# I2C-SignalTestJig.net
KiCad netlist of a schematic drawn in EAGLE
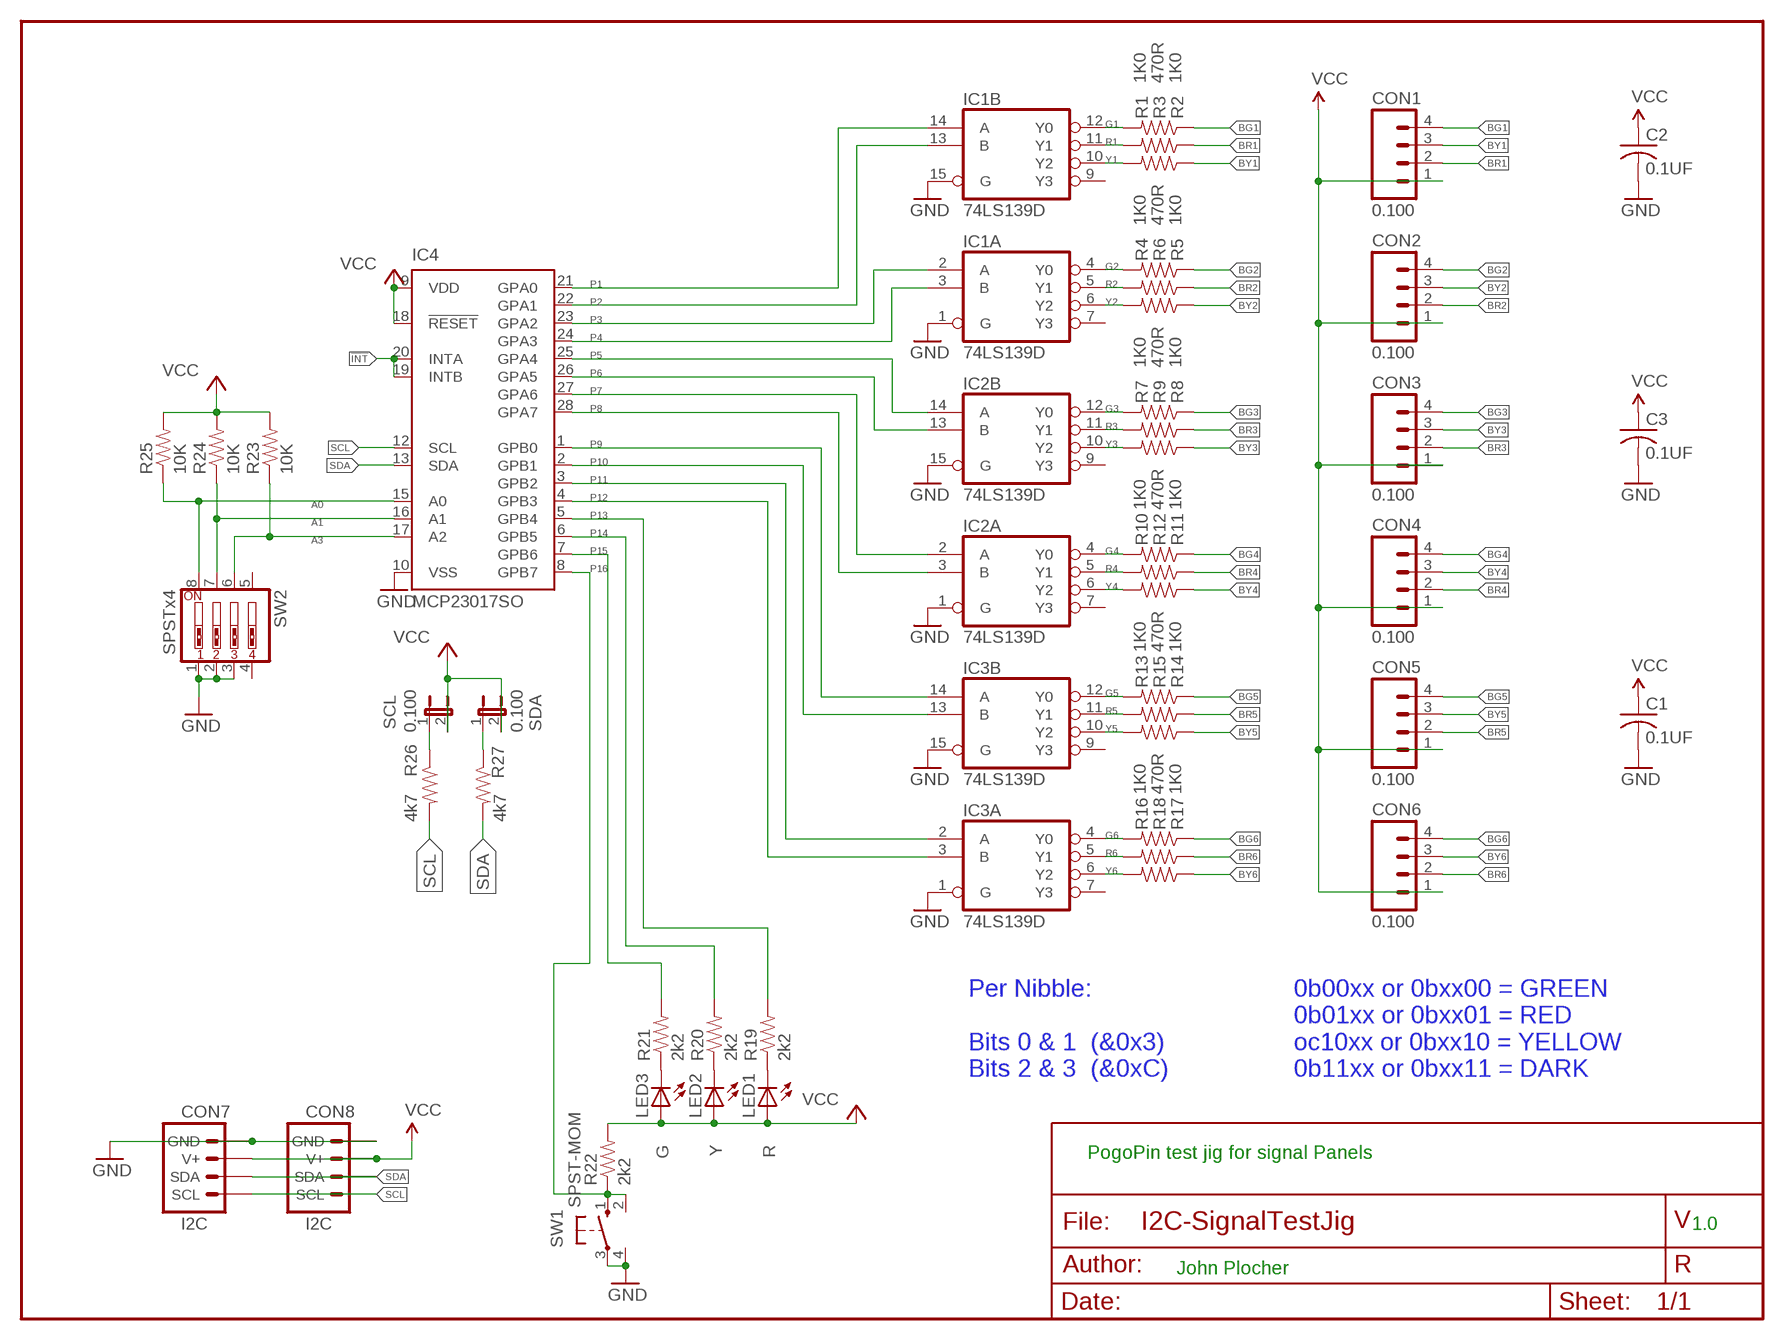
[diagram p0: schematic, sheet 1]

(export (version "E")
  (design (tool "Eeschema 10.0.6"))
  (components
    (comp (ref "C1")
      (value "0.1UF")
      (footprint "eagle-import:0603-CAP")
      (libsource (lib "eagle-import") (part "CAP0603"))
    )
    (comp (ref "C2")
      (value "0.1UF")
      (footprint "eagle-import:0603-CAP")
      (libsource (lib "eagle-import") (part "CAP0603"))
    )
    (comp (ref "C3")
      (value "0.1UF")
      (footprint "eagle-import:0603-CAP")
      (libsource (lib "eagle-import") (part "CAP0603"))
    )
    (comp (ref "CON1")
      (value "0.100")
      (footprint "eagle-import:1X04_LOCK")
      (libsource (lib "eagle-import") (part "CONNECTOR-M04LOCK"))
    )
    (comp (ref "CON2")
      (value "0.100")
      (footprint "eagle-import:1X04_LOCK")
      (libsource (lib "eagle-import") (part "CONNECTOR-M04LOCK"))
    )
    (comp (ref "CON3")
      (value "0.100")
      (footprint "eagle-import:1X04_LOCK")
      (libsource (lib "eagle-import") (part "CONNECTOR-M04LOCK"))
    )
    (comp (ref "CON4")
      (value "0.100")
      (footprint "eagle-import:1X04_LOCK")
      (libsource (lib "eagle-import") (part "CONNECTOR-M04LOCK"))
    )
    (comp (ref "CON5")
      (value "0.100")
      (footprint "eagle-import:1X04_LOCK")
      (libsource (lib "eagle-import") (part "CONNECTOR-M04LOCK"))
    )
    (comp (ref "CON6")
      (value "0.100")
      (footprint "eagle-import:1X04_LOCK")
      (libsource (lib "eagle-import") (part "CONNECTOR-M04LOCK"))
    )
    (comp (ref "CON7")
      (value "I2C")
      (footprint "eagle-import:I2C-L")
      (libsource (lib "eagle-import") (part "CONNECTOR-I2CLEFT"))
    )
    (comp (ref "CON8")
      (value "I2C")
      (footprint "eagle-import:I2C-L")
      (libsource (lib "eagle-import") (part "CONNECTOR-I2CLEFT"))
    )
    (comp (ref "IC1")
      (value "74LS139D")
      (footprint "eagle-import:SO16")
      (libsource (lib "eagle-import") (part "74139DLS"))
    )
    (comp (ref "IC2")
      (value "74LS139D")
      (footprint "eagle-import:SO16")
      (libsource (lib "eagle-import") (part "74139DLS"))
    )
    (comp (ref "IC3")
      (value "74LS139D")
      (footprint "eagle-import:SO16")
      (libsource (lib "eagle-import") (part "74139DLS"))
    )
    (comp (ref "IC4")
      (value "MCP23017SO")
      (footprint "eagle-import:SO28W")
      (fields (field (name "MF") "MICROCHIP") (field (name "MPN") "MCP23017-E/SO"))
      (libsource (lib "eagle-import") (part "MCP23017SO"))
    )
    (comp (ref "LED1")
      (value "R")
      (footprint "eagle-import:0603-LED")
      (libsource (lib "eagle-import") (part "LED0603-LED"))
    )
    (comp (ref "LED2")
      (value "Y")
      (footprint "eagle-import:0603-LED")
      (libsource (lib "eagle-import") (part "LED0603-LED"))
    )
    (comp (ref "LED3")
      (value "G")
      (footprint "eagle-import:0603-LED")
      (libsource (lib "eagle-import") (part "LED0603-LED"))
    )
    (comp (ref "R1")
      (value "1K0")
      (footprint "eagle-import:0805-RES")
      (libsource (lib "eagle-import") (part "R0805-RES"))
    )
    (comp (ref "R2")
      (value "1K0")
      (footprint "eagle-import:0805-RES")
      (libsource (lib "eagle-import") (part "R0805-RES"))
    )
    (comp (ref "R3")
      (value "470R")
      (footprint "eagle-import:0805-RES")
      (libsource (lib "eagle-import") (part "R0805-RES"))
    )
    (comp (ref "R4")
      (value "1K0")
      (footprint "eagle-import:0805-RES")
      (libsource (lib "eagle-import") (part "R0805-RES"))
    )
    (comp (ref "R5")
      (value "1K0")
      (footprint "eagle-import:0805-RES")
      (libsource (lib "eagle-import") (part "R0805-RES"))
    )
    (comp (ref "R6")
      (value "470R")
      (footprint "eagle-import:0805-RES")
      (libsource (lib "eagle-import") (part "R0805-RES"))
    )
    (comp (ref "R7")
      (value "1K0")
      (footprint "eagle-import:0805-RES")
      (libsource (lib "eagle-import") (part "R0805-RES"))
    )
    (comp (ref "R8")
      (value "1K0")
      (footprint "eagle-import:0805-RES")
      (libsource (lib "eagle-import") (part "R0805-RES"))
    )
    (comp (ref "R9")
      (value "470R")
      (footprint "eagle-import:0805-RES")
      (libsource (lib "eagle-import") (part "R0805-RES"))
    )
    (comp (ref "R10")
      (value "1K0")
      (footprint "eagle-import:0805-RES")
      (libsource (lib "eagle-import") (part "R0805-RES"))
    )
    (comp (ref "R11")
      (value "1K0")
      (footprint "eagle-import:0805-RES")
      (libsource (lib "eagle-import") (part "R0805-RES"))
    )
    (comp (ref "R12")
      (value "470R")
      (footprint "eagle-import:0805-RES")
      (libsource (lib "eagle-import") (part "R0805-RES"))
    )
    (comp (ref "R13")
      (value "1K0")
      (footprint "eagle-import:0805-RES")
      (libsource (lib "eagle-import") (part "R0805-RES"))
    )
    (comp (ref "R14")
      (value "1K0")
      (footprint "eagle-import:0805-RES")
      (libsource (lib "eagle-import") (part "R0805-RES"))
    )
    (comp (ref "R15")
      (value "470R")
      (footprint "eagle-import:0805-RES")
      (libsource (lib "eagle-import") (part "R0805-RES"))
    )
    (comp (ref "R16")
      (value "1K0")
      (footprint "eagle-import:0805-RES")
      (libsource (lib "eagle-import") (part "R0805-RES"))
    )
    (comp (ref "R17")
      (value "1K0")
      (footprint "eagle-import:0805-RES")
      (libsource (lib "eagle-import") (part "R0805-RES"))
    )
    (comp (ref "R18")
      (value "470R")
      (footprint "eagle-import:0805-RES")
      (libsource (lib "eagle-import") (part "R0805-RES"))
    )
    (comp (ref "R19")
      (value "2k2")
      (footprint "eagle-import:0603-RES")
      (libsource (lib "eagle-import") (part "R0603-RES"))
    )
    (comp (ref "R20")
      (value "2k2")
      (footprint "eagle-import:0603-RES")
      (libsource (lib "eagle-import") (part "R0603-RES"))
    )
    (comp (ref "R21")
      (value "2k2")
      (footprint "eagle-import:0603-RES")
      (libsource (lib "eagle-import") (part "R0603-RES"))
    )
    (comp (ref "R22")
      (value "2k2")
      (footprint "eagle-import:0603-RES")
      (libsource (lib "eagle-import") (part "R0603-RES"))
    )
    (comp (ref "R23")
      (value "10K")
      (footprint "eagle-import:0603-RES")
      (libsource (lib "eagle-import") (part "R0603-RES"))
    )
    (comp (ref "R24")
      (value "10K")
      (footprint "eagle-import:0603-RES")
      (libsource (lib "eagle-import") (part "R0603-RES"))
    )
    (comp (ref "R25")
      (value "10K")
      (footprint "eagle-import:0603-RES")
      (libsource (lib "eagle-import") (part "R0603-RES"))
    )
    (comp (ref "R26")
      (value "4k7")
      (footprint "eagle-import:0603-RES")
      (libsource (lib "eagle-import") (part "R0603-RES"))
    )
    (comp (ref "R27")
      (value "4k7")
      (footprint "eagle-import:0603-RES")
      (libsource (lib "eagle-import") (part "R0603-RES"))
    )
    (comp (ref "SCL")
      (value "0.100")
      (footprint "eagle-import:1X02_LOCK")
      (libsource (lib "eagle-import") (part "JUMPER-2PTH_LOCK"))
    )
    (comp (ref "SDA")
      (value "0.100")
      (footprint "eagle-import:1X02_LOCK")
      (libsource (lib "eagle-import") (part "JUMPER-2PTH_LOCK"))
    )
    (comp (ref "SW1")
      (value "SPST-MOM")
      (footprint "eagle-import:4P-PTH-6.0X6.0X5.0H")
      (libsource (lib "eagle-import") (part "SWITCH-(ON)SMALLPADS"))
    )
    (comp (ref "SW2")
      (value "SPSTx4")
      (footprint "eagle-import:EDG-04")
      (libsource (lib "eagle-import") (part "SW_DIP-4"))
    )
  )
  (nets
    (net (code "1") (name "/A0") (class "Default")
      (node (ref "IC4") (pin "15") (pinfunction "A0_15") (pintype "input"))
      (node (ref "R25") (pin "1") (pinfunction "1_1") (pintype "passive"))
      (node (ref "SW2") (pin "8") (pinfunction "8_8") (pintype "passive"))
    )
    (net (code "2") (name "/A1") (class "Default")
      (node (ref "IC4") (pin "16") (pinfunction "A1_16") (pintype "input"))
      (node (ref "R24") (pin "1") (pinfunction "1_1") (pintype "passive"))
      (node (ref "SW2") (pin "7") (pinfunction "7_7") (pintype "passive"))
    )
    (net (code "3") (name "/A3") (class "Default")
      (node (ref "IC4") (pin "17") (pinfunction "A2_17") (pintype "input"))
      (node (ref "R23") (pin "1") (pinfunction "1_1") (pintype "passive"))
      (node (ref "SW2") (pin "6") (pinfunction "6_6") (pintype "passive"))
    )
    (net (code "4") (name "/G1") (class "Default")
      (node (ref "IC1") (pin "12") (pinfunction "Y0_12") (pintype "output"))
      (node (ref "R1") (pin "2") (pinfunction "2_2") (pintype "passive"))
    )
    (net (code "5") (name "/G2") (class "Default")
      (node (ref "IC1") (pin "4") (pinfunction "Y0_4") (pintype "output"))
      (node (ref "R4") (pin "2") (pinfunction "2_2") (pintype "passive"))
    )
    (net (code "6") (name "/G3") (class "Default")
      (node (ref "IC2") (pin "12") (pinfunction "Y0_12") (pintype "output"))
      (node (ref "R7") (pin "2") (pinfunction "2_2") (pintype "passive"))
    )
    (net (code "7") (name "/G4") (class "Default")
      (node (ref "IC2") (pin "4") (pinfunction "Y0_4") (pintype "output"))
      (node (ref "R10") (pin "2") (pinfunction "2_2") (pintype "passive"))
    )
    (net (code "8") (name "/G5") (class "Default")
      (node (ref "IC3") (pin "12") (pinfunction "Y0_12") (pintype "output"))
      (node (ref "R13") (pin "2") (pinfunction "2_2") (pintype "passive"))
    )
    (net (code "9") (name "/G6") (class "Default")
      (node (ref "IC3") (pin "4") (pinfunction "Y0_4") (pintype "output"))
      (node (ref "R16") (pin "2") (pinfunction "2_2") (pintype "passive"))
    )
    (net (code "10") (name "/P1") (class "Default")
      (node (ref "IC1") (pin "14") (pinfunction "A_14") (pintype "input"))
      (node (ref "IC4") (pin "21") (pinfunction "GPA0_21") (pintype "bidirectional"))
    )
    (net (code "11") (name "/P2") (class "Default")
      (node (ref "IC1") (pin "13") (pinfunction "B_13") (pintype "input"))
      (node (ref "IC4") (pin "22") (pinfunction "GPA1_22") (pintype "bidirectional"))
    )
    (net (code "12") (name "/P3") (class "Default")
      (node (ref "IC1") (pin "2") (pinfunction "A_2") (pintype "input"))
      (node (ref "IC4") (pin "23") (pinfunction "GPA2_23") (pintype "bidirectional"))
    )
    (net (code "13") (name "/P4") (class "Default")
      (node (ref "IC1") (pin "3") (pinfunction "B_3") (pintype "input"))
      (node (ref "IC4") (pin "24") (pinfunction "GPA3_24") (pintype "bidirectional"))
    )
    (net (code "14") (name "/P5") (class "Default")
      (node (ref "IC2") (pin "14") (pinfunction "A_14") (pintype "input"))
      (node (ref "IC4") (pin "25") (pinfunction "GPA4_25") (pintype "bidirectional"))
    )
    (net (code "15") (name "/P6") (class "Default")
      (node (ref "IC2") (pin "13") (pinfunction "B_13") (pintype "input"))
      (node (ref "IC4") (pin "26") (pinfunction "GPA5_26") (pintype "bidirectional"))
    )
    (net (code "16") (name "/P7") (class "Default")
      (node (ref "IC2") (pin "2") (pinfunction "A_2") (pintype "input"))
      (node (ref "IC4") (pin "27") (pinfunction "GPA6_27") (pintype "bidirectional"))
    )
    (net (code "17") (name "/P8") (class "Default")
      (node (ref "IC2") (pin "3") (pinfunction "B_3") (pintype "input"))
      (node (ref "IC4") (pin "28") (pinfunction "GPA7_28") (pintype "bidirectional"))
    )
    (net (code "18") (name "/P9") (class "Default")
      (node (ref "IC3") (pin "14") (pinfunction "A_14") (pintype "input"))
      (node (ref "IC4") (pin "1") (pinfunction "GPB0_1") (pintype "bidirectional"))
    )
    (net (code "19") (name "/P10") (class "Default")
      (node (ref "IC3") (pin "13") (pinfunction "B_13") (pintype "input"))
      (node (ref "IC4") (pin "2") (pinfunction "GPB1_2") (pintype "bidirectional"))
    )
    (net (code "20") (name "/P11") (class "Default")
      (node (ref "IC3") (pin "2") (pinfunction "A_2") (pintype "input"))
      (node (ref "IC4") (pin "3") (pinfunction "GPB2_3") (pintype "bidirectional"))
    )
    (net (code "21") (name "/P12") (class "Default")
      (node (ref "IC3") (pin "3") (pinfunction "B_3") (pintype "input"))
      (node (ref "IC4") (pin "4") (pinfunction "GPB3_4") (pintype "bidirectional"))
    )
    (net (code "22") (name "/P13") (class "Default")
      (node (ref "IC4") (pin "5") (pinfunction "GPB4_5") (pintype "bidirectional"))
      (node (ref "R19") (pin "2") (pinfunction "2_2") (pintype "passive"))
    )
    (net (code "23") (name "/P14") (class "Default")
      (node (ref "IC4") (pin "6") (pinfunction "GPB5_6") (pintype "bidirectional"))
      (node (ref "R20") (pin "2") (pinfunction "2_2") (pintype "passive"))
    )
    (net (code "24") (name "/P15") (class "Default")
      (node (ref "IC4") (pin "7") (pinfunction "GPB6_7") (pintype "bidirectional"))
      (node (ref "R21") (pin "2") (pinfunction "2_2") (pintype "passive"))
    )
    (net (code "25") (name "/P16") (class "Default")
      (node (ref "IC4") (pin "8") (pinfunction "GPB7_8") (pintype "bidirectional"))
      (node (ref "R22") (pin "1") (pinfunction "1_1") (pintype "passive"))
      (node (ref "SW1") (pin "1") (pinfunction "S_1") (pintype "passive"))
      (node (ref "SW1") (pin "2") (pinfunction "S1_2") (pintype "passive"))
    )
    (net (code "26") (name "/R1") (class "Default")
      (node (ref "IC1") (pin "11") (pinfunction "Y1_11") (pintype "output"))
      (node (ref "R3") (pin "2") (pinfunction "2_2") (pintype "passive"))
    )
    (net (code "27") (name "/R2") (class "Default")
      (node (ref "IC1") (pin "5") (pinfunction "Y1_5") (pintype "output"))
      (node (ref "R6") (pin "2") (pinfunction "2_2") (pintype "passive"))
    )
    (net (code "28") (name "/R3") (class "Default")
      (node (ref "IC2") (pin "11") (pinfunction "Y1_11") (pintype "output"))
      (node (ref "R9") (pin "2") (pinfunction "2_2") (pintype "passive"))
    )
    (net (code "29") (name "/R4") (class "Default")
      (node (ref "IC2") (pin "5") (pinfunction "Y1_5") (pintype "output"))
      (node (ref "R12") (pin "2") (pinfunction "2_2") (pintype "passive"))
    )
    (net (code "30") (name "/R5") (class "Default")
      (node (ref "IC3") (pin "11") (pinfunction "Y1_11") (pintype "output"))
      (node (ref "R15") (pin "2") (pinfunction "2_2") (pintype "passive"))
    )
    (net (code "31") (name "/R6") (class "Default")
      (node (ref "IC3") (pin "5") (pinfunction "Y1_5") (pintype "output"))
      (node (ref "R18") (pin "2") (pinfunction "2_2") (pintype "passive"))
    )
    (net (code "32") (name "/Y1") (class "Default")
      (node (ref "IC1") (pin "10") (pinfunction "Y2_10") (pintype "output"))
      (node (ref "R2") (pin "2") (pinfunction "2_2") (pintype "passive"))
    )
    (net (code "33") (name "/Y2") (class "Default")
      (node (ref "IC1") (pin "6") (pinfunction "Y2_6") (pintype "output"))
      (node (ref "R5") (pin "2") (pinfunction "2_2") (pintype "passive"))
    )
    (net (code "34") (name "/Y3") (class "Default")
      (node (ref "IC2") (pin "10") (pinfunction "Y2_10") (pintype "output"))
      (node (ref "R8") (pin "2") (pinfunction "2_2") (pintype "passive"))
    )
    (net (code "35") (name "/Y4") (class "Default")
      (node (ref "IC2") (pin "6") (pinfunction "Y2_6") (pintype "output"))
      (node (ref "R11") (pin "2") (pinfunction "2_2") (pintype "passive"))
    )
    (net (code "36") (name "/Y5") (class "Default")
      (node (ref "IC3") (pin "10") (pinfunction "Y2_10") (pintype "output"))
      (node (ref "R14") (pin "2") (pinfunction "2_2") (pintype "passive"))
    )
    (net (code "37") (name "/Y6") (class "Default")
      (node (ref "IC3") (pin "6") (pinfunction "Y2_6") (pintype "output"))
      (node (ref "R17") (pin "2") (pinfunction "2_2") (pintype "passive"))
    )
    (net (code "38") (name "/~{INT}") (class "Default")
      (node (ref "IC4") (pin "19") (pinfunction "INTB_19") (pintype "output"))
      (node (ref "IC4") (pin "20") (pinfunction "INTA_20") (pintype "output"))
    )
    (net (code "39") (name "BG1") (class "Default")
      (node (ref "CON1") (pin "4") (pinfunction "4_4") (pintype "passive"))
      (node (ref "R1") (pin "1") (pinfunction "1_1") (pintype "passive"))
    )
    (net (code "40") (name "BG2") (class "Default")
      (node (ref "CON2") (pin "4") (pinfunction "4_4") (pintype "passive"))
      (node (ref "R4") (pin "1") (pinfunction "1_1") (pintype "passive"))
    )
    (net (code "41") (name "BG3") (class "Default")
      (node (ref "CON3") (pin "4") (pinfunction "4_4") (pintype "passive"))
      (node (ref "R7") (pin "1") (pinfunction "1_1") (pintype "passive"))
    )
    (net (code "42") (name "BG4") (class "Default")
      (node (ref "CON4") (pin "4") (pinfunction "4_4") (pintype "passive"))
      (node (ref "R10") (pin "1") (pinfunction "1_1") (pintype "passive"))
    )
    (net (code "43") (name "BG5") (class "Default")
      (node (ref "CON5") (pin "4") (pinfunction "4_4") (pintype "passive"))
      (node (ref "R13") (pin "1") (pinfunction "1_1") (pintype "passive"))
    )
    (net (code "44") (name "BG6") (class "Default")
      (node (ref "CON6") (pin "4") (pinfunction "4_4") (pintype "passive"))
      (node (ref "R16") (pin "1") (pinfunction "1_1") (pintype "passive"))
    )
    (net (code "45") (name "BR1") (class "Default")
      (node (ref "CON1") (pin "2") (pinfunction "2_2") (pintype "passive"))
      (node (ref "R3") (pin "1") (pinfunction "1_1") (pintype "passive"))
    )
    (net (code "46") (name "BR2") (class "Default")
      (node (ref "CON2") (pin "2") (pinfunction "2_2") (pintype "passive"))
      (node (ref "R6") (pin "1") (pinfunction "1_1") (pintype "passive"))
    )
    (net (code "47") (name "BR3") (class "Default")
      (node (ref "CON3") (pin "2") (pinfunction "2_2") (pintype "passive"))
      (node (ref "R9") (pin "1") (pinfunction "1_1") (pintype "passive"))
    )
    (net (code "48") (name "BR4") (class "Default")
      (node (ref "CON4") (pin "2") (pinfunction "2_2") (pintype "passive"))
      (node (ref "R12") (pin "1") (pinfunction "1_1") (pintype "passive"))
    )
    (net (code "49") (name "BR5") (class "Default")
      (node (ref "CON5") (pin "2") (pinfunction "2_2") (pintype "passive"))
      (node (ref "R15") (pin "1") (pinfunction "1_1") (pintype "passive"))
    )
    (net (code "50") (name "BR6") (class "Default")
      (node (ref "CON6") (pin "2") (pinfunction "2_2") (pintype "passive"))
      (node (ref "R18") (pin "1") (pinfunction "1_1") (pintype "passive"))
    )
    (net (code "51") (name "BY1") (class "Default")
      (node (ref "CON1") (pin "3") (pinfunction "3_3") (pintype "passive"))
      (node (ref "R2") (pin "1") (pinfunction "1_1") (pintype "passive"))
    )
    (net (code "52") (name "BY2") (class "Default")
      (node (ref "CON2") (pin "3") (pinfunction "3_3") (pintype "passive"))
      (node (ref "R5") (pin "1") (pinfunction "1_1") (pintype "passive"))
    )
    (net (code "53") (name "BY3") (class "Default")
      (node (ref "CON3") (pin "3") (pinfunction "3_3") (pintype "passive"))
      (node (ref "R8") (pin "1") (pinfunction "1_1") (pintype "passive"))
    )
    (net (code "54") (name "BY4") (class "Default")
      (node (ref "CON4") (pin "3") (pinfunction "3_3") (pintype "passive"))
      (node (ref "R11") (pin "1") (pinfunction "1_1") (pintype "passive"))
    )
    (net (code "55") (name "BY5") (class "Default")
      (node (ref "CON5") (pin "3") (pinfunction "3_3") (pintype "passive"))
      (node (ref "R14") (pin "1") (pinfunction "1_1") (pintype "passive"))
    )
    (net (code "56") (name "BY6") (class "Default")
      (node (ref "CON6") (pin "3") (pinfunction "3_3") (pintype "passive"))
      (node (ref "R17") (pin "1") (pinfunction "1_1") (pintype "passive"))
    )
    (net (code "57") (name "GND") (class "Default")
      (node (ref "C1") (pin "2") (pinfunction "2_2") (pintype "passive"))
      (node (ref "C2") (pin "2") (pinfunction "2_2") (pintype "passive"))
      (node (ref "C3") (pin "2") (pinfunction "2_2") (pintype "passive"))
      (node (ref "CON7") (pin "GND") (pinfunction "GND_GND") (pintype "passive"))
      (node (ref "CON7") (pin "GND@1") (pinfunction "GND_GND@1") (pintype "passive"))
      (node (ref "CON8") (pin "GND") (pinfunction "GND_GND") (pintype "passive"))
      (node (ref "CON8") (pin "GND@1") (pinfunction "GND_GND@1") (pintype "passive"))
      (node (ref "IC1") (pin "1") (pinfunction "G_1") (pintype "input"))
      (node (ref "IC1") (pin "15") (pinfunction "G_15") (pintype "input"))
      (node (ref "IC2") (pin "1") (pinfunction "G_1") (pintype "input"))
      (node (ref "IC2") (pin "15") (pinfunction "G_15") (pintype "input"))
      (node (ref "IC3") (pin "1") (pinfunction "G_1") (pintype "input"))
      (node (ref "IC3") (pin "15") (pinfunction "G_15") (pintype "input"))
      (node (ref "IC4") (pin "10") (pinfunction "VSS_10") (pintype "power_in"))
      (node (ref "SW1") (pin "3") (pinfunction "P_3") (pintype "passive"))
      (node (ref "SW1") (pin "4") (pinfunction "P1_4") (pintype "passive"))
      (node (ref "SW2") (pin "1") (pinfunction "1_1") (pintype "passive"))
      (node (ref "SW2") (pin "2") (pinfunction "2_2") (pintype "passive"))
      (node (ref "SW2") (pin "3") (pinfunction "3_3") (pintype "passive"))
    )
    (net (code "58") (name "Net-(LED1-PadC)") (class "Default")
      (node (ref "LED1") (pin "C") (pinfunction "C_C") (pintype "passive"))
      (node (ref "R19") (pin "1") (pinfunction "1_1") (pintype "passive"))
    )
    (net (code "59") (name "Net-(LED2-PadC)") (class "Default")
      (node (ref "LED2") (pin "C") (pinfunction "C_C") (pintype "passive"))
      (node (ref "R20") (pin "1") (pinfunction "1_1") (pintype "passive"))
    )
    (net (code "60") (name "Net-(LED3-PadC)") (class "Default")
      (node (ref "LED3") (pin "C") (pinfunction "C_C") (pintype "passive"))
      (node (ref "R21") (pin "1") (pinfunction "1_1") (pintype "passive"))
    )
    (net (code "61") (name "Net-(R26-Pad1)") (class "Default")
      (node (ref "R26") (pin "1") (pinfunction "1_1") (pintype "passive"))
      (node (ref "SCL") (pin "1") (pinfunction "1_1") (pintype "passive"))
    )
    (net (code "62") (name "Net-(R27-Pad1)") (class "Default")
      (node (ref "R27") (pin "1") (pinfunction "1_1") (pintype "passive"))
      (node (ref "SDA") (pin "1") (pinfunction "1_1") (pintype "passive"))
    )
    (net (code "63") (name "SCL") (class "Default")
      (node (ref "CON7") (pin "SCL") (pinfunction "SCL_SCL") (pintype "passive"))
      (node (ref "CON7") (pin "SCL@1") (pinfunction "SCL_SCL@1") (pintype "passive"))
      (node (ref "CON8") (pin "SCL") (pinfunction "SCL_SCL") (pintype "passive"))
      (node (ref "CON8") (pin "SCL@1") (pinfunction "SCL_SCL@1") (pintype "passive"))
      (node (ref "IC4") (pin "12") (pinfunction "SCL_12") (pintype "input"))
      (node (ref "R26") (pin "2") (pinfunction "2_2") (pintype "passive"))
    )
    (net (code "64") (name "SDA") (class "Default")
      (node (ref "CON7") (pin "SDA") (pinfunction "SDA_SDA") (pintype "passive"))
      (node (ref "CON7") (pin "SDA@1") (pinfunction "SDA_SDA@1") (pintype "passive"))
      (node (ref "CON8") (pin "SDA") (pinfunction "SDA_SDA") (pintype "passive"))
      (node (ref "CON8") (pin "SDA@1") (pinfunction "SDA_SDA@1") (pintype "passive"))
      (node (ref "IC4") (pin "13") (pinfunction "SDA_13") (pintype "bidirectional"))
      (node (ref "R27") (pin "2") (pinfunction "2_2") (pintype "passive"))
    )
    (net (code "65") (name "VCC") (class "Default")
      (node (ref "C1") (pin "1") (pinfunction "1_1") (pintype "passive"))
      (node (ref "C2") (pin "1") (pinfunction "1_1") (pintype "passive"))
      (node (ref "C3") (pin "1") (pinfunction "1_1") (pintype "passive"))
      (node (ref "CON1") (pin "1") (pinfunction "1_1") (pintype "passive"))
      (node (ref "CON2") (pin "1") (pinfunction "1_1") (pintype "passive"))
      (node (ref "CON3") (pin "1") (pinfunction "1_1") (pintype "passive"))
      (node (ref "CON4") (pin "1") (pinfunction "1_1") (pintype "passive"))
      (node (ref "CON5") (pin "1") (pinfunction "1_1") (pintype "passive"))
      (node (ref "CON6") (pin "1") (pinfunction "1_1") (pintype "passive"))
      (node (ref "CON7") (pin "V+") (pinfunction "V+_V+") (pintype "passive"))
      (node (ref "CON7") (pin "V+@1") (pinfunction "V+_V+@1") (pintype "passive"))
      (node (ref "CON8") (pin "V+") (pinfunction "V+_V+") (pintype "passive"))
      (node (ref "CON8") (pin "V+@1") (pinfunction "V+_V+@1") (pintype "passive"))
      (node (ref "IC4") (pin "18") (pinfunction "~{RESET}_18") (pintype "input"))
      (node (ref "IC4") (pin "9") (pinfunction "VDD_9") (pintype "power_in"))
      (node (ref "LED1") (pin "A") (pinfunction "A_A") (pintype "passive"))
      (node (ref "LED2") (pin "A") (pinfunction "A_A") (pintype "passive"))
      (node (ref "LED3") (pin "A") (pinfunction "A_A") (pintype "passive"))
      (node (ref "R22") (pin "2") (pinfunction "2_2") (pintype "passive"))
      (node (ref "R23") (pin "2") (pinfunction "2_2") (pintype "passive"))
      (node (ref "R24") (pin "2") (pinfunction "2_2") (pintype "passive"))
      (node (ref "R25") (pin "2") (pinfunction "2_2") (pintype "passive"))
      (node (ref "SCL") (pin "2") (pinfunction "2_2") (pintype "passive"))
      (node (ref "SDA") (pin "2") (pinfunction "2_2") (pintype "passive"))
    )
    (net (code "66") (name "unconnected-(IC1A-Y3-Pad7)") (class "Default")
      (node (ref "IC1") (pin "7") (pinfunction "Y3_7") (pintype "output"))
    )
    (net (code "67") (name "unconnected-(IC1B-Y3-Pad9)") (class "Default")
      (node (ref "IC1") (pin "9") (pinfunction "Y3_9") (pintype "output"))
    )
    (net (code "68") (name "unconnected-(IC2A-Y3-Pad7)") (class "Default")
      (node (ref "IC2") (pin "7") (pinfunction "Y3_7") (pintype "output"))
    )
    (net (code "69") (name "unconnected-(IC2B-Y3-Pad9)") (class "Default")
      (node (ref "IC2") (pin "9") (pinfunction "Y3_9") (pintype "output"))
    )
    (net (code "70") (name "unconnected-(IC3A-Y3-Pad7)") (class "Default")
      (node (ref "IC3") (pin "7") (pinfunction "Y3_7") (pintype "output"))
    )
    (net (code "71") (name "unconnected-(IC3B-Y3-Pad9)") (class "Default")
      (node (ref "IC3") (pin "9") (pinfunction "Y3_9") (pintype "output"))
    )
    (net (code "72") (name "unconnected-(SW2-Pad4)") (class "Default")
      (node (ref "SW2") (pin "4") (pinfunction "4_4") (pintype "passive"))
    )
    (net (code "73") (name "unconnected-(SW2-Pad5)") (class "Default")
      (node (ref "SW2") (pin "5") (pinfunction "5_5") (pintype "passive"))
    )
  )
)
